# Josytick_Rev_J.net
KiCad netlist of a schematic drawn in EAGLE
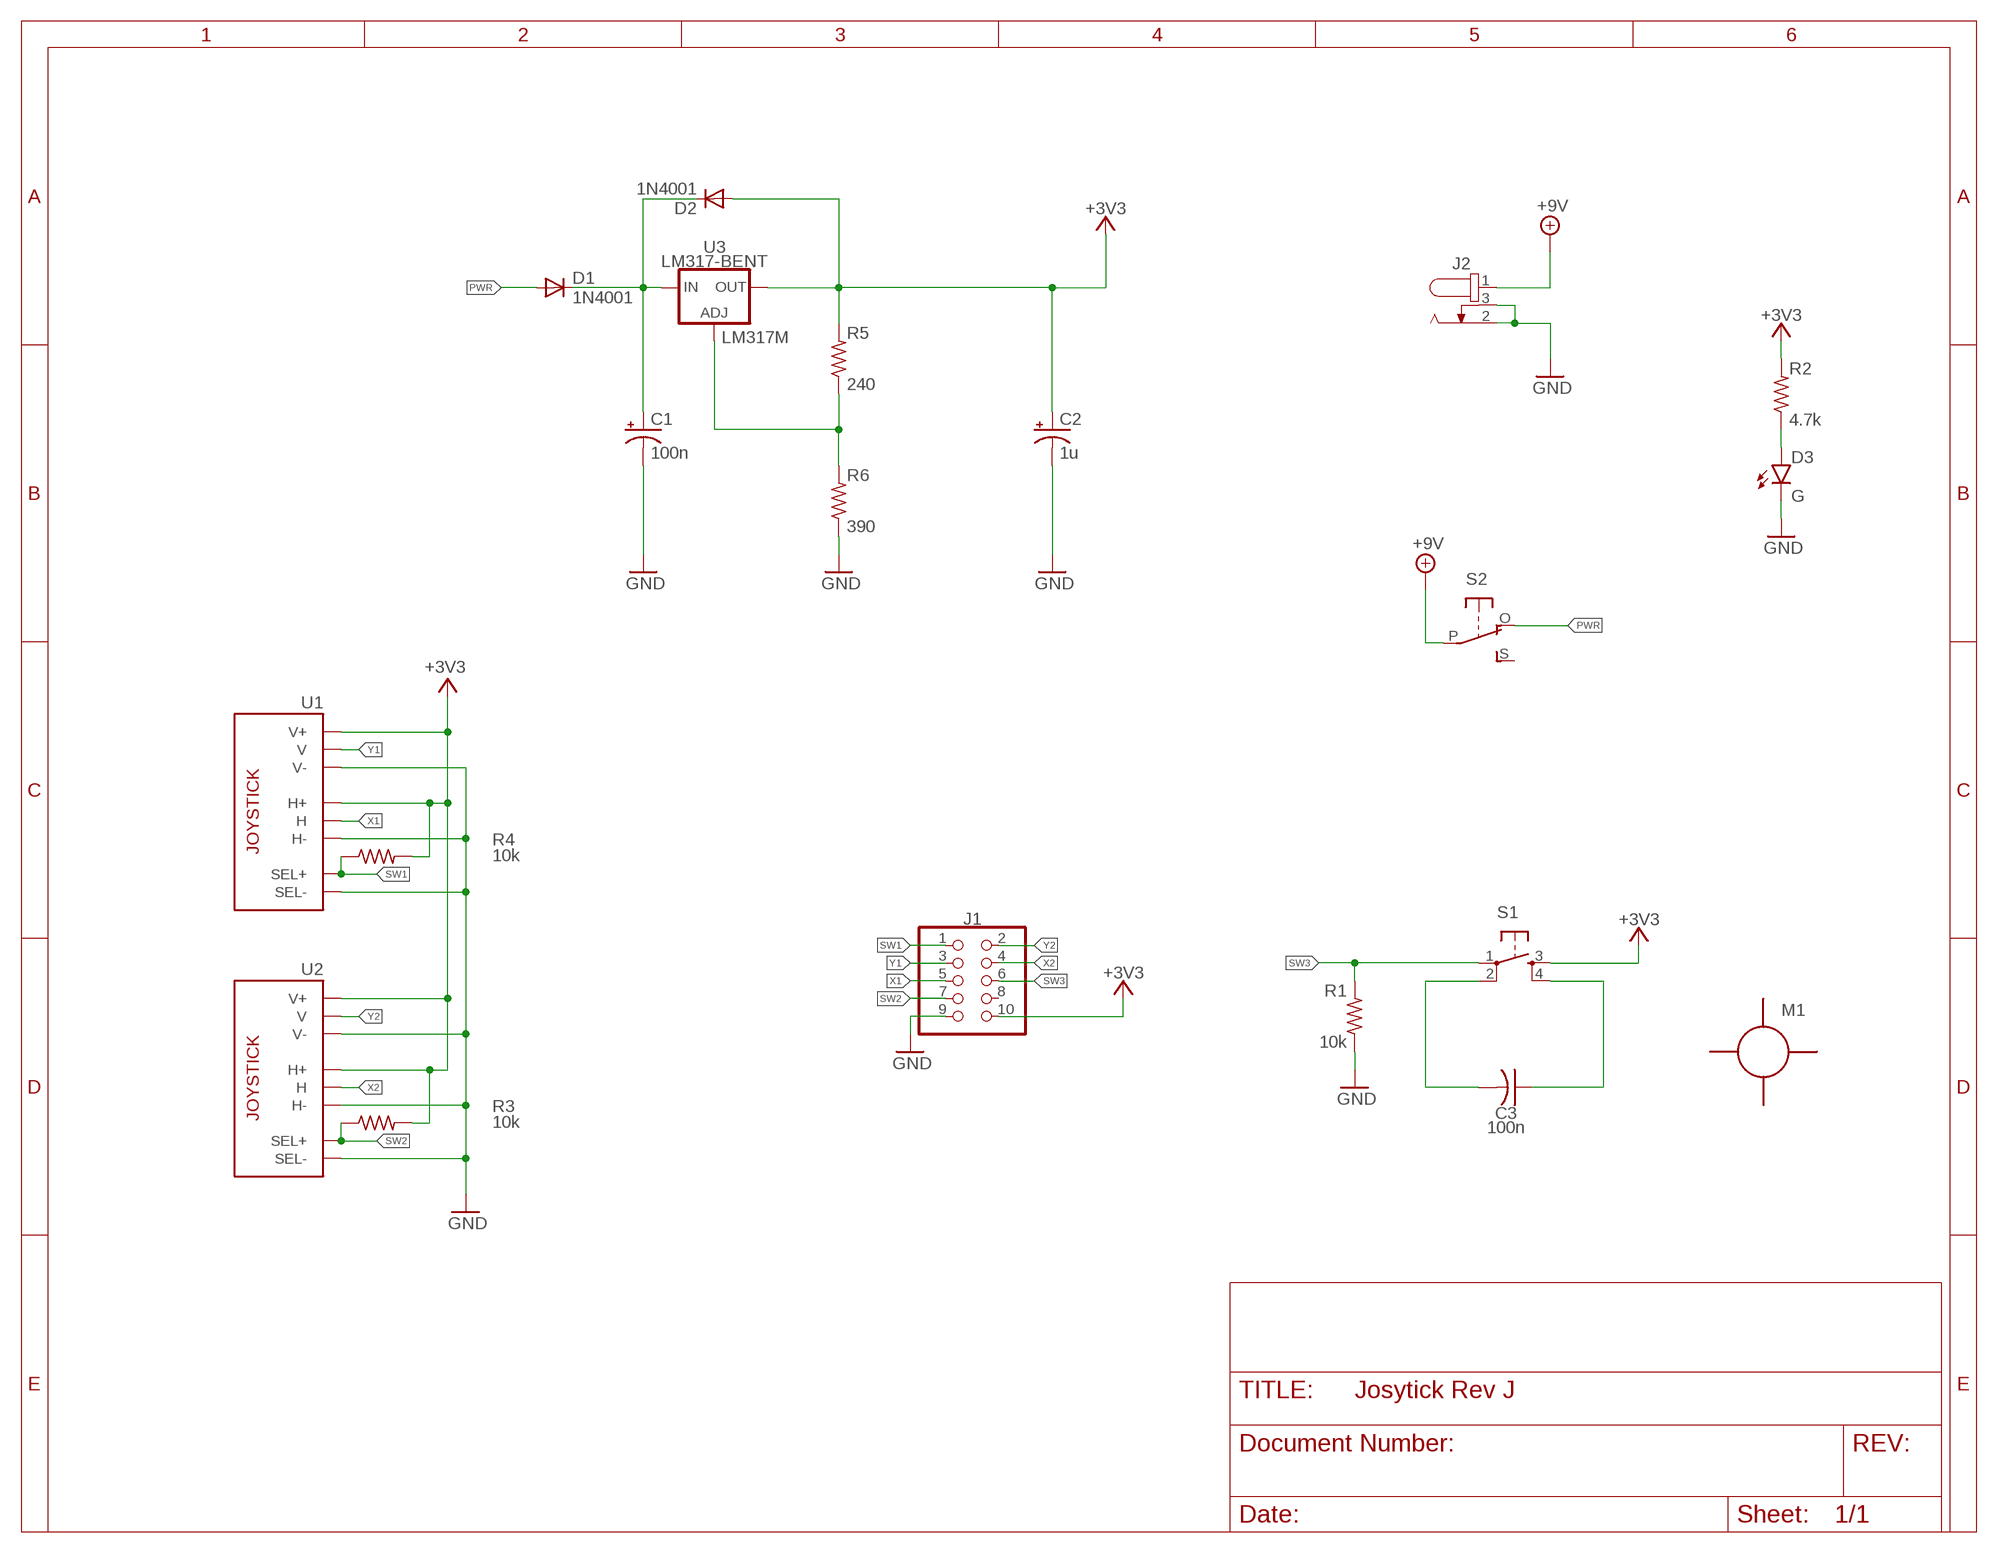
[diagram p0: schematic, sheet 1]

(export (version "E")
  (design (tool "Eeschema 10.0.6"))
  (components
    (comp (ref "C1")
      (value "100n")
      (footprint "eagle-import:E2-4")
      (libsource (lib "eagle-import") (part "ELECTROLYTIC-CAPACITOR2-4"))
    )
    (comp (ref "C2")
      (value "1u")
      (footprint "eagle-import:E2-4")
      (libsource (lib "eagle-import") (part "ELECTROLYTIC-CAPACITOR2-4"))
    )
    (comp (ref "C3")
      (value "100n")
      (footprint "eagle-import:C050-024X044")
      (libsource (lib "eagle-import") (part "THT-CER-CAPACITOR"))
    )
    (comp (ref "D1")
      (value "1N4001")
      (footprint "eagle-import:DO41-10")
      (libsource (lib "eagle-import") (part "1N4000"))
    )
    (comp (ref "D2")
      (value "1N4001")
      (footprint "eagle-import:DO41-10")
      (libsource (lib "eagle-import") (part "1N4000"))
    )
    (comp (ref "D3")
      (value "G")
      (footprint "eagle-import:LED5MM")
      (libsource (lib "eagle-import") (part "LED"))
    )
    (comp (ref "J1")
      (value "RIBBON-2X5")
      (footprint "eagle-import:057-010-1")
      (libsource (lib "eagle-import") (part "RIBBON-2X5"))
    )
    (comp (ref "J2")
      (value "694106301002")
      (footprint "eagle-import:694106301002")
      (libsource (lib "eagle-import") (part "694106301002"))
    )
    (comp (ref "M1")
      (value "9V-HOLDERM2.5")
      (footprint "eagle-import:9V-HOLDER-M2.5")
      (libsource (lib "eagle-import") (part "9V-HOLDERM2.5"))
    )
    (comp (ref "R1")
      (value "10k")
      (footprint "eagle-import:0207_10")
      (libsource (lib "eagle-import") (part "RESISTOR"))
    )
    (comp (ref "R2")
      (value "4.7k")
      (footprint "eagle-import:0207_10")
      (libsource (lib "eagle-import") (part "RESISTOR"))
    )
    (comp (ref "R3")
      (value "10k")
      (footprint "eagle-import:0207_10")
      (libsource (lib "eagle-import") (part "RESISTOR"))
    )
    (comp (ref "R4")
      (value "10k")
      (footprint "eagle-import:0207_10")
      (libsource (lib "eagle-import") (part "RESISTOR"))
    )
    (comp (ref "R5")
      (value "240")
      (footprint "eagle-import:0207_10")
      (libsource (lib "eagle-import") (part "RESISTOR"))
    )
    (comp (ref "R6")
      (value "390")
      (footprint "eagle-import:0207_10")
      (libsource (lib "eagle-import") (part "RESISTOR"))
    )
    (comp (ref "S1")
      (value "TACTILE-BUTTON40XX")
      (footprint "eagle-import:B3F-40XX")
      (fields (field (name "SPICEPREFIX") "S"))
      (libsource (lib "eagle-import") (part "TACTILE-BUTTON40XX"))
    )
    (comp (ref "S2")
      (value "SLIDE-SWITCHSIDE")
      (footprint "eagle-import:EG1270-90")
      (libsource (lib "eagle-import") (part "SLIDE-SWITCHSIDE"))
    )
    (comp (ref "U1")
      (value "JOYSTICK")
      (footprint "eagle-import:JOYSTICK")
      (libsource (lib "eagle-import") (part "JOYSTICK"))
    )
    (comp (ref "U2")
      (value "JOYSTICK")
      (footprint "eagle-import:JOYSTICK")
      (libsource (lib "eagle-import") (part "JOYSTICK"))
    )
    (comp (ref "U3")
      (value "LM317-BENT")
      (footprint "eagle-import:T03B")
      (fields (field (name "PARTNUMBER") "LM317M"))
      (libsource (lib "eagle-import") (part "LM317BENT"))
    )
  )
  (nets
    (net (code "1") (name "+3V3") (class "Default")
      (node (ref "C2") (pin "+") (pinfunction "+_+") (pintype "passive"))
      (node (ref "D2") (pin "A") (pinfunction "A_A") (pintype "passive"))
      (node (ref "J1") (pin "10") (pinfunction "10_10") (pintype "passive"))
      (node (ref "R2") (pin "2") (pinfunction "2_2") (pintype "passive"))
      (node (ref "R3") (pin "2") (pinfunction "2_2") (pintype "passive"))
      (node (ref "R4") (pin "2") (pinfunction "2_2") (pintype "passive"))
      (node (ref "R5") (pin "2") (pinfunction "2_2") (pintype "passive"))
      (node (ref "S1") (pin "3") (pinfunction "S_3") (pintype "passive"))
      (node (ref "U1") (pin "H1") (pinfunction "H+_H1") (pintype "bidirectional"))
      (node (ref "U1") (pin "V1") (pinfunction "V+_V1") (pintype "bidirectional"))
      (node (ref "U2") (pin "H1") (pinfunction "H+_H1") (pintype "bidirectional"))
      (node (ref "U2") (pin "V1") (pinfunction "V+_V1") (pintype "bidirectional"))
      (node (ref "U3") (pin "2") (pinfunction "OUT_2") (pintype "passive"))
    )
    (net (code "2") (name "+9V") (class "Default")
      (node (ref "J2") (pin "1") (pinfunction "1_1") (pintype "passive"))
      (node (ref "S2") (pin "P") (pinfunction "P_P") (pintype "passive"))
    )
    (net (code "3") (name "GND") (class "Default")
      (node (ref "C1") (pin "-") (pinfunction "-_-") (pintype "passive"))
      (node (ref "C2") (pin "-") (pinfunction "-_-") (pintype "passive"))
      (node (ref "D3") (pin "K") (pinfunction "C_K") (pintype "passive"))
      (node (ref "J1") (pin "9") (pinfunction "9_9") (pintype "passive"))
      (node (ref "J2") (pin "2") (pinfunction "2_2") (pintype "passive"))
      (node (ref "J2") (pin "3") (pinfunction "3_3") (pintype "passive"))
      (node (ref "R1") (pin "1") (pinfunction "1_1") (pintype "passive"))
      (node (ref "R6") (pin "1") (pinfunction "1_1") (pintype "passive"))
      (node (ref "U1") (pin "B2A") (pinfunction "SEL-_B2A") (pintype "bidirectional"))
      (node (ref "U1") (pin "H3") (pinfunction "H-_H3") (pintype "bidirectional"))
      (node (ref "U1") (pin "V3") (pinfunction "V-_V3") (pintype "bidirectional"))
      (node (ref "U2") (pin "B2A") (pinfunction "SEL-_B2A") (pintype "bidirectional"))
      (node (ref "U2") (pin "H3") (pinfunction "H-_H3") (pintype "bidirectional"))
      (node (ref "U2") (pin "V3") (pinfunction "V-_V3") (pintype "bidirectional"))
    )
    (net (code "4") (name "Net-(D3-PadA)") (class "Default")
      (node (ref "D3") (pin "A") (pinfunction "A_A") (pintype "passive"))
      (node (ref "R2") (pin "1") (pinfunction "1_1") (pintype "passive"))
    )
    (net (code "5") (name "Net-(S1-P1)") (class "Default")
      (node (ref "C3") (pin "2") (pinfunction "2_2") (pintype "passive"))
      (node (ref "S1") (pin "2") (pinfunction "P1_2") (pintype "passive"))
    )
    (net (code "6") (name "Net-(S1-S1)") (class "Default")
      (node (ref "C3") (pin "1") (pinfunction "1_1") (pintype "passive"))
      (node (ref "S1") (pin "4") (pinfunction "S1_4") (pintype "passive"))
    )
    (net (code "7") (name "Net-(U3-ADJ)") (class "Default")
      (node (ref "R5") (pin "1") (pinfunction "1_1") (pintype "passive"))
      (node (ref "R6") (pin "2") (pinfunction "2_2") (pintype "passive"))
      (node (ref "U3") (pin "1") (pinfunction "ADJ_1") (pintype "input"))
    )
    (net (code "8") (name "Net-(U3-IN)") (class "Default")
      (node (ref "C1") (pin "+") (pinfunction "+_+") (pintype "passive"))
      (node (ref "D1") (pin "C") (pinfunction "C_C") (pintype "passive"))
      (node (ref "D2") (pin "C") (pinfunction "C_C") (pintype "passive"))
      (node (ref "U3") (pin "3") (pinfunction "IN_3") (pintype "input"))
    )
    (net (code "9") (name "PWR") (class "Default")
      (node (ref "D1") (pin "A") (pinfunction "A_A") (pintype "passive"))
      (node (ref "S2") (pin "O") (pinfunction "O_O") (pintype "passive"))
    )
    (net (code "10") (name "SW1") (class "Default")
      (node (ref "J1") (pin "1") (pinfunction "1_1") (pintype "passive"))
      (node (ref "R4") (pin "1") (pinfunction "1_1") (pintype "passive"))
      (node (ref "U1") (pin "B1A") (pinfunction "SEL+_B1A") (pintype "bidirectional"))
    )
    (net (code "11") (name "SW2") (class "Default")
      (node (ref "J1") (pin "7") (pinfunction "7_7") (pintype "passive"))
      (node (ref "R3") (pin "1") (pinfunction "1_1") (pintype "passive"))
      (node (ref "U2") (pin "B1A") (pinfunction "SEL+_B1A") (pintype "bidirectional"))
    )
    (net (code "12") (name "SW3") (class "Default")
      (node (ref "J1") (pin "6") (pinfunction "6_6") (pintype "passive"))
      (node (ref "R1") (pin "2") (pinfunction "2_2") (pintype "passive"))
      (node (ref "S1") (pin "1") (pinfunction "P_1") (pintype "passive"))
    )
    (net (code "13") (name "X1") (class "Default")
      (node (ref "J1") (pin "5") (pinfunction "5_5") (pintype "passive"))
      (node (ref "U1") (pin "H2") (pinfunction "H_H2") (pintype "bidirectional"))
    )
    (net (code "14") (name "X2") (class "Default")
      (node (ref "J1") (pin "4") (pinfunction "4_4") (pintype "passive"))
      (node (ref "U2") (pin "H2") (pinfunction "H_H2") (pintype "bidirectional"))
    )
    (net (code "15") (name "Y1") (class "Default")
      (node (ref "J1") (pin "3") (pinfunction "3_3") (pintype "passive"))
      (node (ref "U1") (pin "V2") (pinfunction "V_V2") (pintype "bidirectional"))
    )
    (net (code "16") (name "Y2") (class "Default")
      (node (ref "J1") (pin "2") (pinfunction "2_2") (pintype "passive"))
      (node (ref "U2") (pin "V2") (pinfunction "V_V2") (pintype "bidirectional"))
    )
    (net (code "17") (name "unconnected-(J1-Pad8)") (class "Default")
      (node (ref "J1") (pin "8") (pinfunction "8_8") (pintype "passive"))
    )
    (net (code "18") (name "unconnected-(S2-PadS)") (class "Default")
      (node (ref "S2") (pin "S") (pinfunction "S_S") (pintype "passive"))
    )
  )
)
